# ScouseTom_CS_Shield_R3.net
KiCad netlist of a schematic drawn in EAGLE
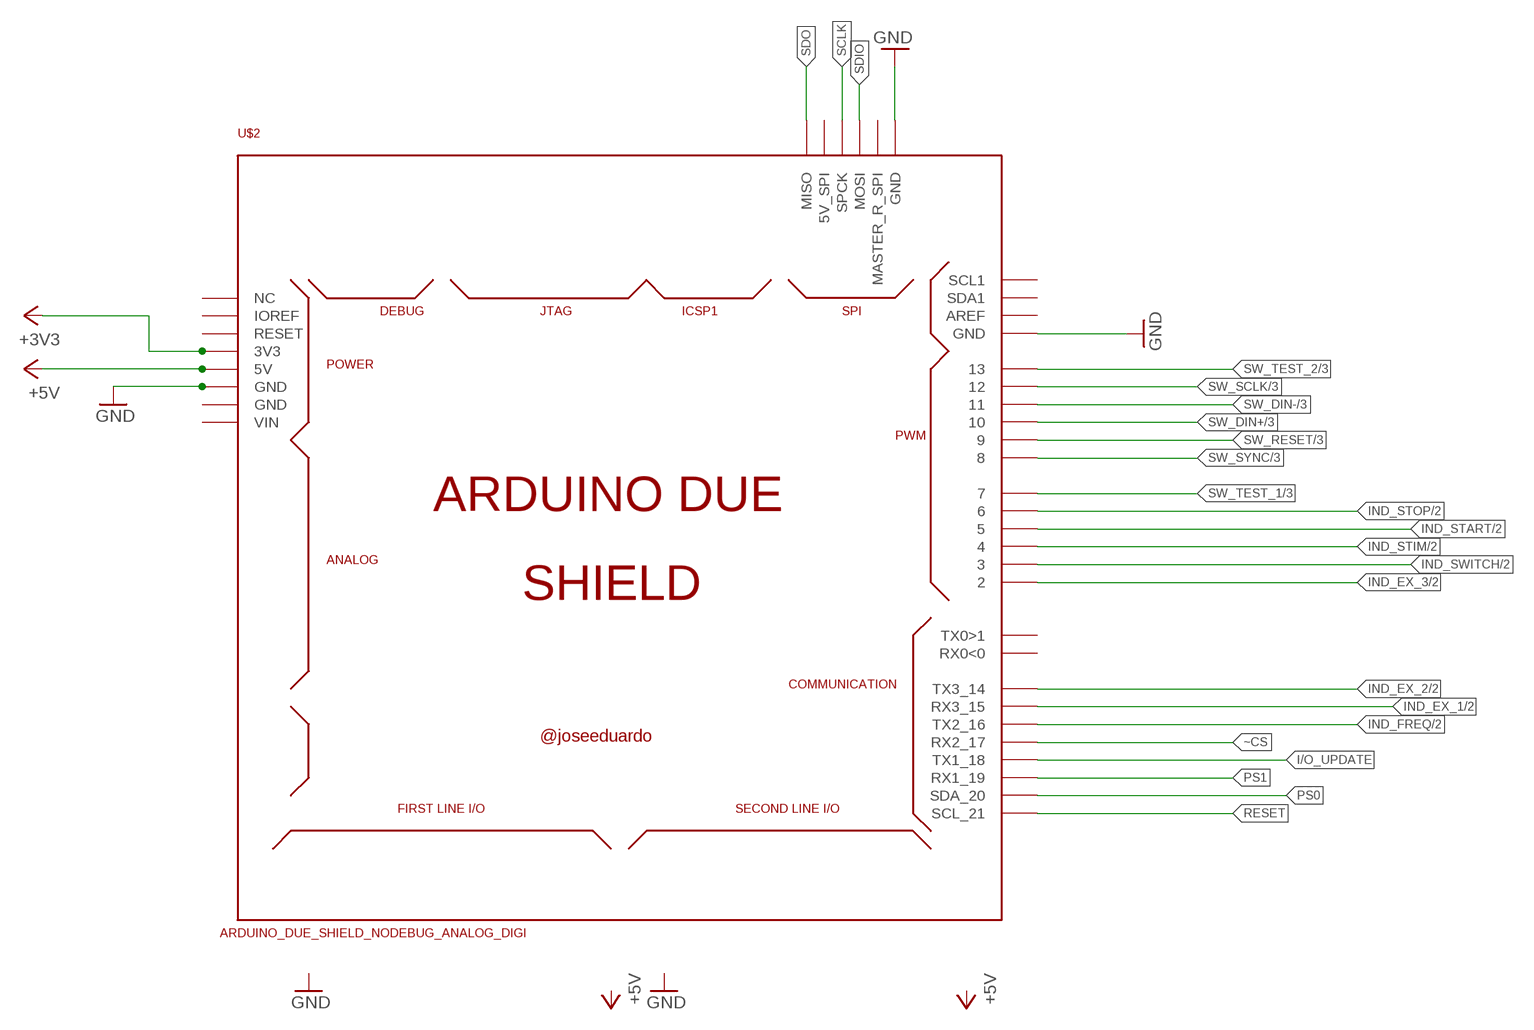
[diagram p0: schematic, sheet 1]
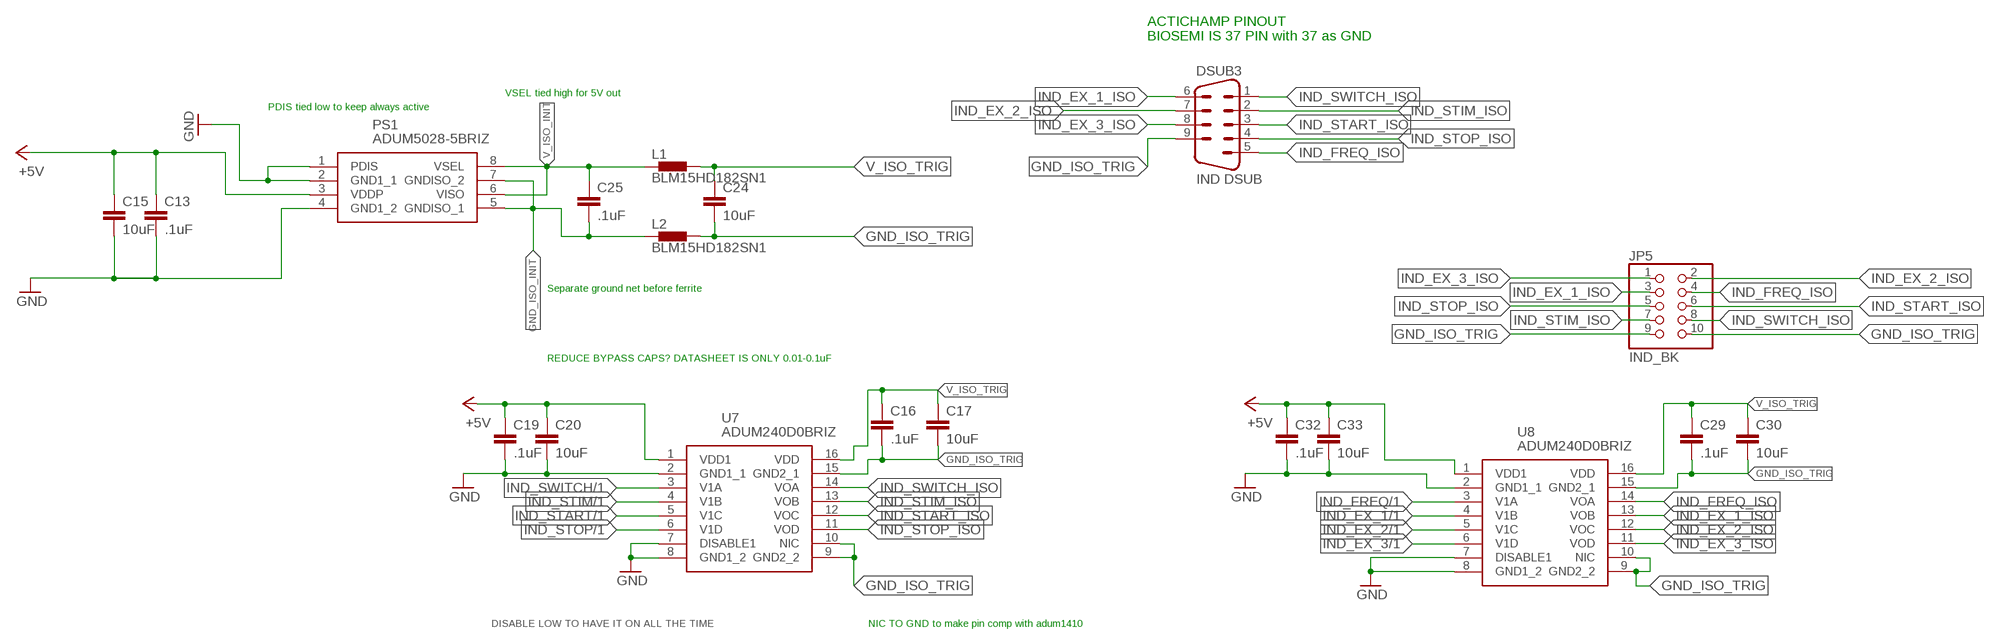
[diagram p1: schematic, sheet 2]
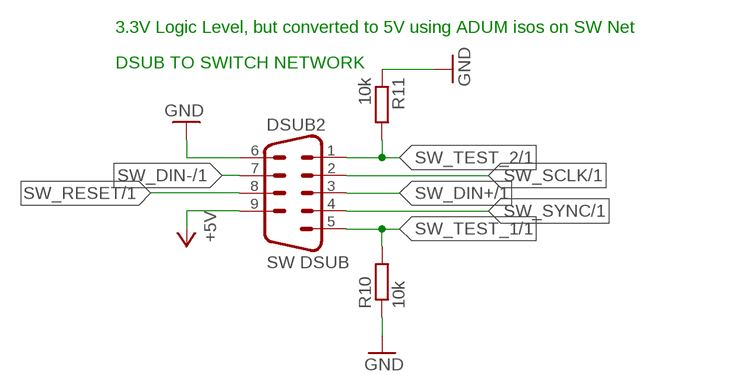
[diagram p2: schematic, sheet 3]
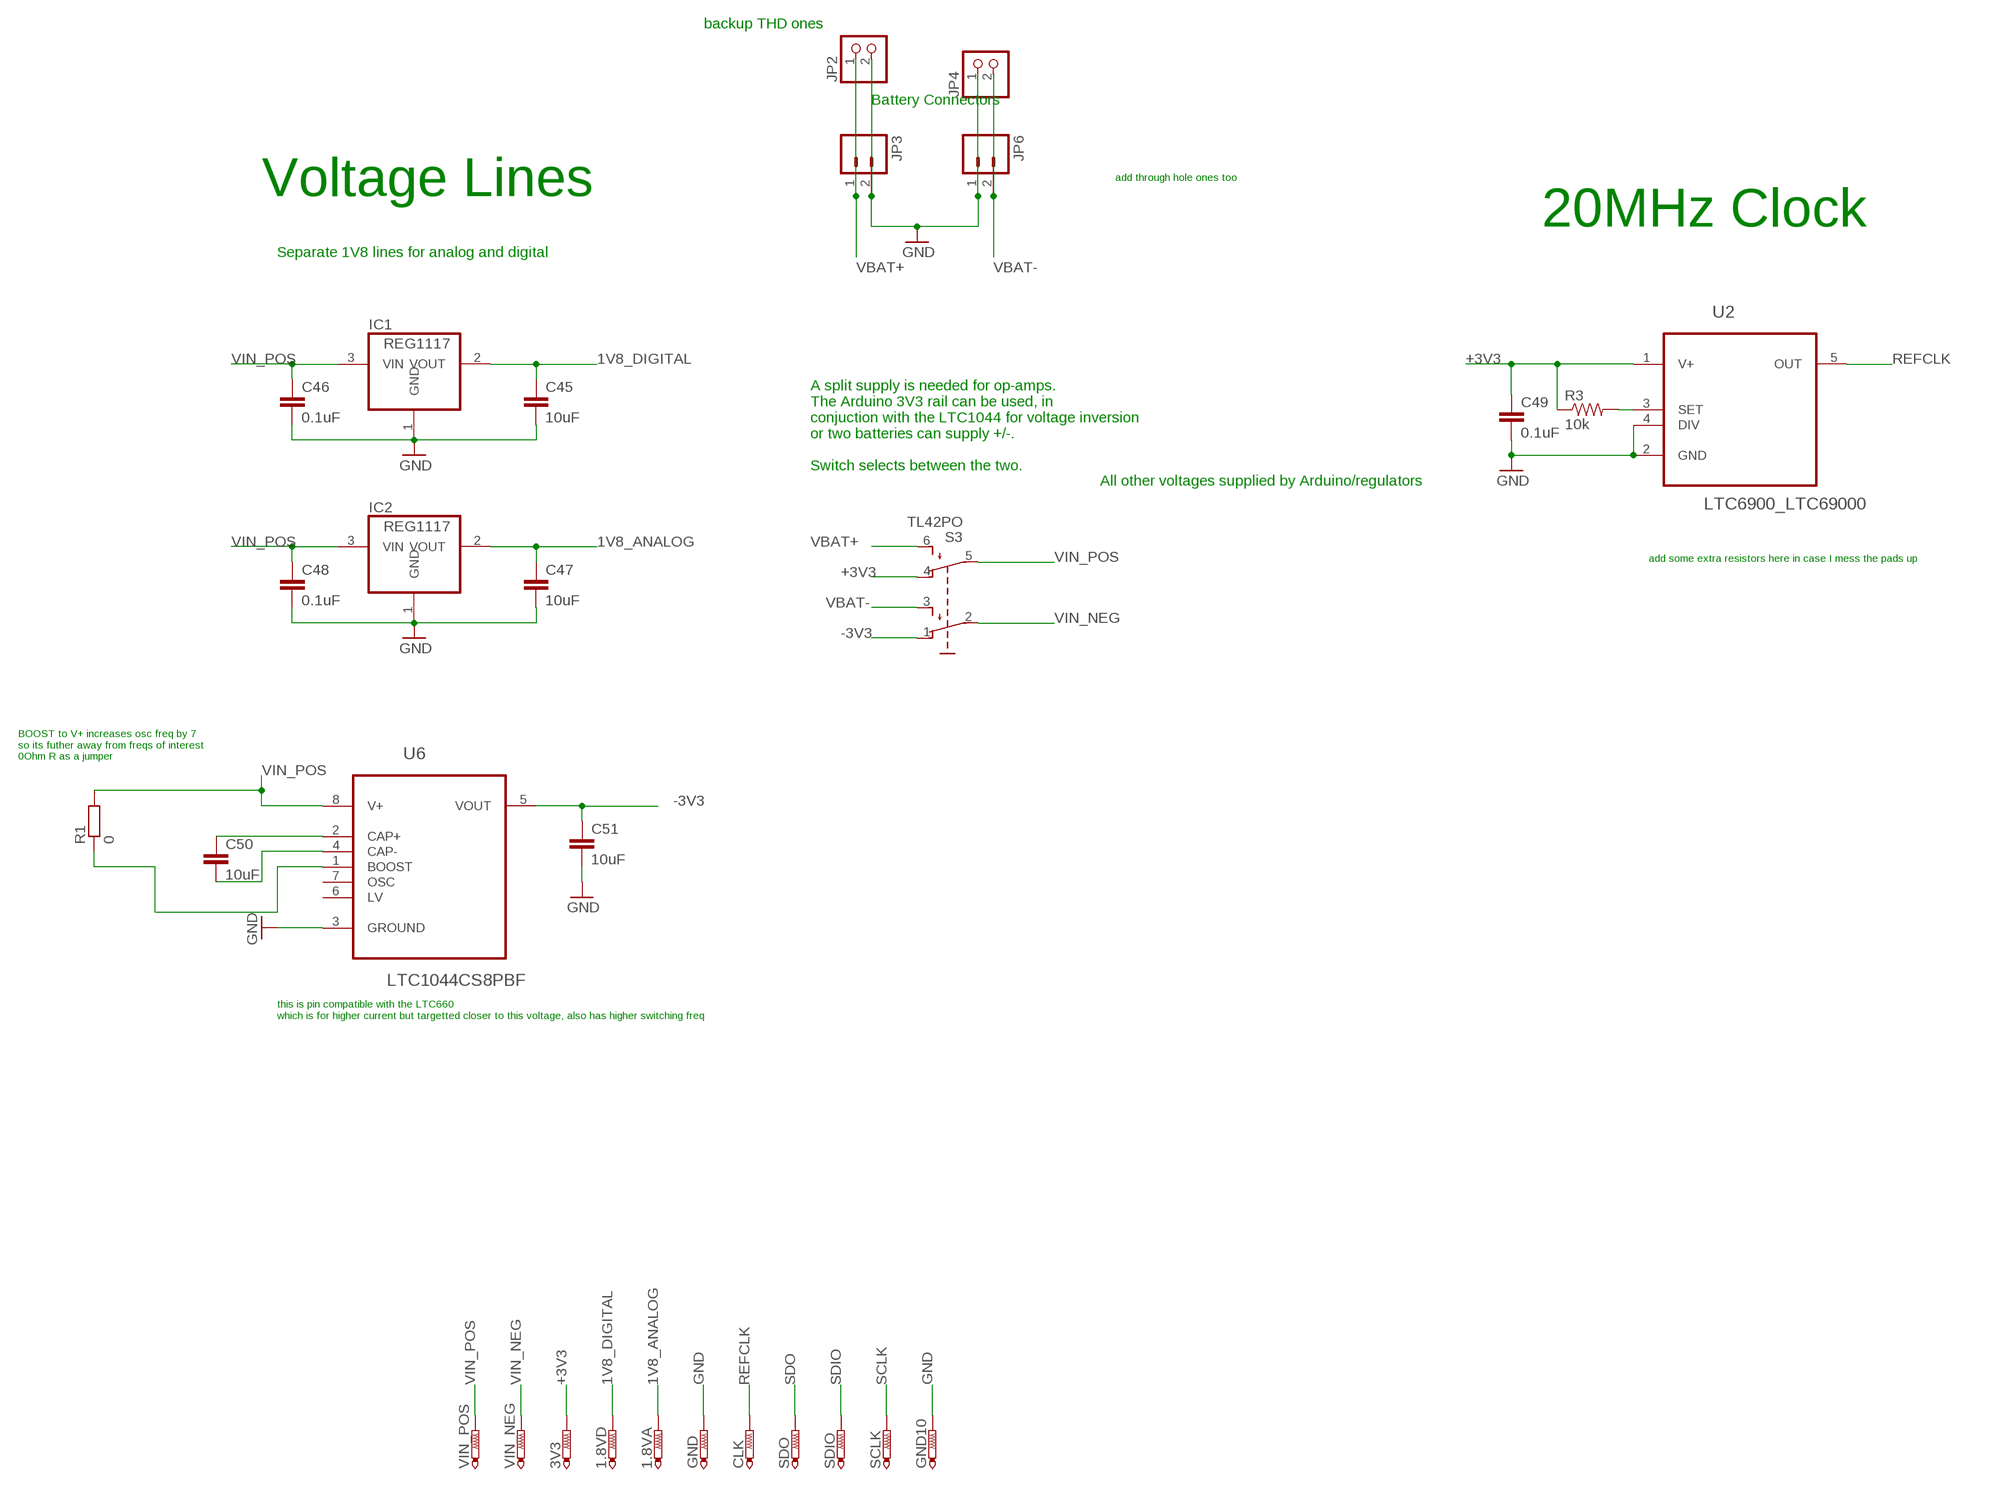
[diagram p3: schematic, sheet 4]
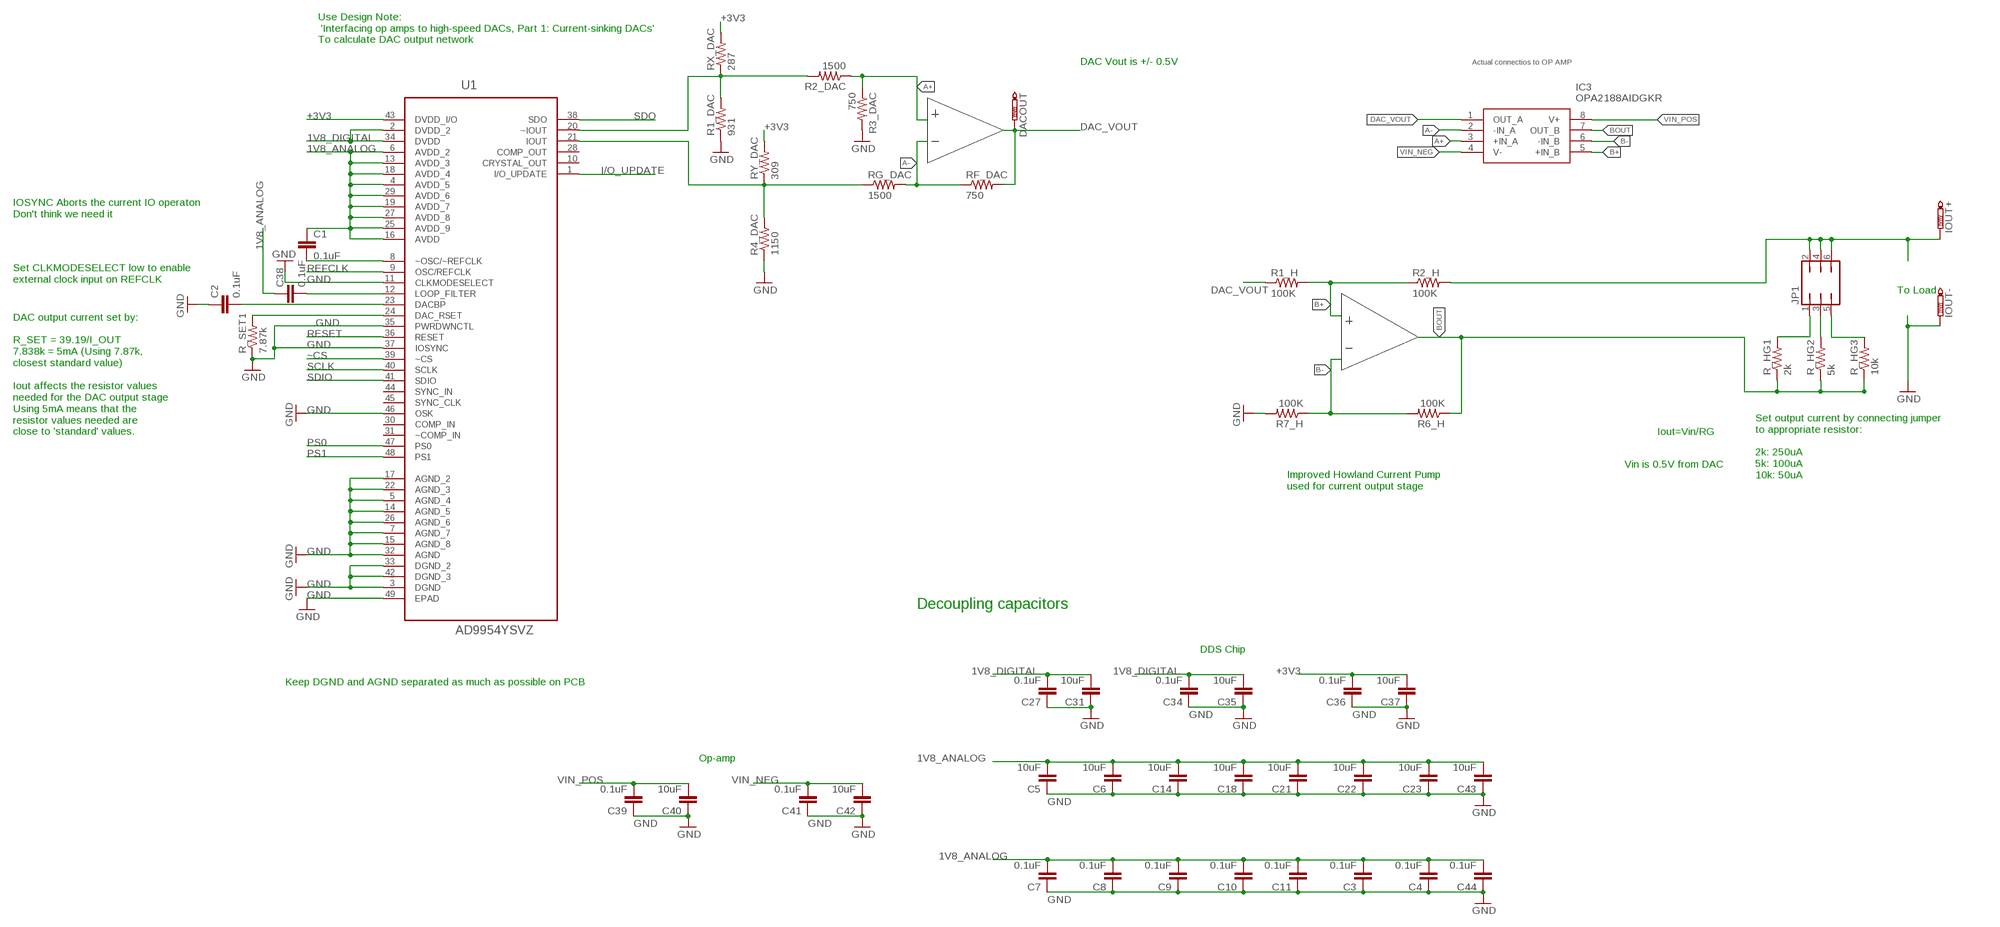
[diagram p4: schematic, sheet 5]

(export (version "E")
  (design (tool "Eeschema 10.0.6"))
  (components
    (comp (ref "C13")
      (value ".1uF")
      (footprint "eagle-import:C0603")
      (libsource (lib "eagle-import") (part "C-EUC0603"))
    )
    (comp (ref "C15")
      (value "10uF")
      (footprint "eagle-import:C0603")
      (libsource (lib "eagle-import") (part "C-EUC0603"))
    )
    (comp (ref "C16")
      (value ".1uF")
      (footprint "eagle-import:C0603")
      (libsource (lib "eagle-import") (part "C-EUC0603"))
    )
    (comp (ref "C17")
      (value "10uF")
      (footprint "eagle-import:C0603")
      (libsource (lib "eagle-import") (part "C-EUC0603"))
    )
    (comp (ref "C19")
      (value ".1uF")
      (footprint "eagle-import:C0603")
      (libsource (lib "eagle-import") (part "C-EUC0603"))
    )
    (comp (ref "C20")
      (value "10uF")
      (footprint "eagle-import:C0603")
      (libsource (lib "eagle-import") (part "C-EUC0603"))
    )
    (comp (ref "C24")
      (value "10uF")
      (footprint "eagle-import:C0603")
      (libsource (lib "eagle-import") (part "C-EUC0603"))
    )
    (comp (ref "C25")
      (value ".1uF")
      (footprint "eagle-import:C0603")
      (libsource (lib "eagle-import") (part "C-EUC0603"))
    )
    (comp (ref "C29")
      (value ".1uF")
      (footprint "eagle-import:C0603")
      (libsource (lib "eagle-import") (part "C-EUC0603"))
    )
    (comp (ref "C30")
      (value "10uF")
      (footprint "eagle-import:C0603")
      (libsource (lib "eagle-import") (part "C-EUC0603"))
    )
    (comp (ref "C32")
      (value ".1uF")
      (footprint "eagle-import:C0603")
      (libsource (lib "eagle-import") (part "C-EUC0603"))
    )
    (comp (ref "C33")
      (value "10uF")
      (footprint "eagle-import:C0603")
      (libsource (lib "eagle-import") (part "C-EUC0603"))
    )
    (comp (ref "DSUB3")
      (value "IND DSUB")
      (footprint "eagle-import:DSUB9")
      (libsource (lib "eagle-import") (part "ScouseTom_New_DSUB9RA"))
    )
    (comp (ref "JP5")
      (value "IND_BK")
      (footprint "eagle-import:2X05")
      (libsource (lib "eagle-import") (part "PINHD-2X5"))
    )
    (comp (ref "L1")
      (value "BLM15HD182SN1")
      (footprint "eagle-import:0402")
      (libsource (lib "eagle-import") (part "BLM15HD182SN1"))
    )
    (comp (ref "L2")
      (value "BLM15HD182SN1")
      (footprint "eagle-import:0402")
      (libsource (lib "eagle-import") (part "BLM15HD182SN1"))
    )
    (comp (ref "PS1")
      (value "ADUM5028-5BRIZ")
      (footprint "eagle-import:SOIC127P1031X265-8N")
      (fields (field (name "MOUSER_PART_NUMBER") "584-ADUM5028-5BRIZ"))
      (libsource (lib "eagle-import") (part "ADUM5028-5BRIZ"))
    )
    (comp (ref "U7")
      (value "ADUM240D0BRIZ")
      (footprint "eagle-import:SOIC127P1032X265-16N")
      (libsource (lib "eagle-import") (part "ADUM240D0BRIZ"))
    )
    (comp (ref "U8")
      (value "ADUM240D0BRIZ")
      (footprint "eagle-import:SOIC127P1032X265-16N")
      (libsource (lib "eagle-import") (part "ADUM240D0BRIZ"))
    )
    (comp (ref "U$2")
      (value "ARDUINO_DUE_SHIELD_NODEBUG_ANALOG_DIGI")
      (footprint "eagle-import:ARDUINO_DUE_SHIELD_NODEBUG_ANALOG_DIG")
      (libsource (lib "eagle-import") (part "ARDUINO_DUE_SHIELD_NODEBUG_ANALOG_DIGI"))
    )
    (comp (ref "C1")
      (value "0.1uF")
      (footprint "eagle-import:C0603")
      (libsource (lib "eagle-import") (part "C-EUC0603"))
    )
    (comp (ref "C2")
      (value "0.1uF")
      (footprint "eagle-import:C0603")
      (libsource (lib "eagle-import") (part "C-EUC0603"))
    )
    (comp (ref "C3")
      (value "0.1uF")
      (footprint "eagle-import:C0603")
      (libsource (lib "eagle-import") (part "C-EUC0603"))
    )
    (comp (ref "C4")
      (value "0.1uF")
      (footprint "eagle-import:C0603")
      (libsource (lib "eagle-import") (part "C-EUC0603"))
    )
    (comp (ref "C5")
      (value "10uF")
      (footprint "eagle-import:C0603")
      (libsource (lib "eagle-import") (part "C-EUC0603"))
    )
    (comp (ref "C6")
      (value "10uF")
      (footprint "eagle-import:C0603")
      (libsource (lib "eagle-import") (part "C-EUC0603"))
    )
    (comp (ref "C7")
      (value "0.1uF")
      (footprint "eagle-import:C0603")
      (libsource (lib "eagle-import") (part "C-EUC0603"))
    )
    (comp (ref "C8")
      (value "0.1uF")
      (footprint "eagle-import:C0603")
      (libsource (lib "eagle-import") (part "C-EUC0603"))
    )
    (comp (ref "C9")
      (value "0.1uF")
      (footprint "eagle-import:C0603")
      (libsource (lib "eagle-import") (part "C-EUC0603"))
    )
    (comp (ref "C10")
      (value "0.1uF")
      (footprint "eagle-import:C0603")
      (libsource (lib "eagle-import") (part "C-EUC0603"))
    )
    (comp (ref "C11")
      (value "0.1uF")
      (footprint "eagle-import:C0603")
      (libsource (lib "eagle-import") (part "C-EUC0603"))
    )
    (comp (ref "C14")
      (value "10uF")
      (footprint "eagle-import:C0603")
      (libsource (lib "eagle-import") (part "C-EUC0603"))
    )
    (comp (ref "C18")
      (value "10uF")
      (footprint "eagle-import:C0603")
      (libsource (lib "eagle-import") (part "C-EUC0603"))
    )
    (comp (ref "C21")
      (value "10uF")
      (footprint "eagle-import:C0603")
      (libsource (lib "eagle-import") (part "C-EUC0603"))
    )
    (comp (ref "C22")
      (value "10uF")
      (footprint "eagle-import:C0603")
      (libsource (lib "eagle-import") (part "C-EUC0603"))
    )
    (comp (ref "C23")
      (value "10uF")
      (footprint "eagle-import:C0603")
      (libsource (lib "eagle-import") (part "C-EUC0603"))
    )
    (comp (ref "C27")
      (value "0.1uF")
      (footprint "eagle-import:C0603")
      (libsource (lib "eagle-import") (part "C-EUC0603"))
    )
    (comp (ref "C31")
      (value "10uF")
      (footprint "eagle-import:C0603")
      (libsource (lib "eagle-import") (part "C-EUC0603"))
    )
    (comp (ref "C34")
      (value "0.1uF")
      (footprint "eagle-import:C0603")
      (libsource (lib "eagle-import") (part "C-EUC0603"))
    )
    (comp (ref "C35")
      (value "10uF")
      (footprint "eagle-import:C0603")
      (libsource (lib "eagle-import") (part "C-EUC0603"))
    )
    (comp (ref "C36")
      (value "0.1uF")
      (footprint "eagle-import:C0603")
      (libsource (lib "eagle-import") (part "C-EUC0603"))
    )
    (comp (ref "C37")
      (value "10uF")
      (footprint "eagle-import:C0603")
      (libsource (lib "eagle-import") (part "C-EUC0603"))
    )
    (comp (ref "C38")
      (value "0.1uF")
      (footprint "eagle-import:C0603")
      (libsource (lib "eagle-import") (part "C-EUC0603"))
    )
    (comp (ref "C39")
      (value "0.1uF")
      (footprint "eagle-import:C0603")
      (libsource (lib "eagle-import") (part "C-EUC0603"))
    )
    (comp (ref "C40")
      (value "10uF")
      (footprint "eagle-import:C0603")
      (libsource (lib "eagle-import") (part "C-EUC0603"))
    )
    (comp (ref "C41")
      (value "0.1uF")
      (footprint "eagle-import:C0603")
      (libsource (lib "eagle-import") (part "C-EUC0603"))
    )
    (comp (ref "C42")
      (value "10uF")
      (footprint "eagle-import:C0603")
      (libsource (lib "eagle-import") (part "C-EUC0603"))
    )
    (comp (ref "C43")
      (value "10uF")
      (footprint "eagle-import:C0603")
      (libsource (lib "eagle-import") (part "C-EUC0603"))
    )
    (comp (ref "C44")
      (value "0.1uF")
      (footprint "eagle-import:C0603")
      (libsource (lib "eagle-import") (part "C-EUC0603"))
    )
    (comp (ref "DACOUT")
      (value "PTR1PAD1-13")
      (footprint "eagle-import:P1-13")
      (libsource (lib "eagle-import") (part "PTR1PAD1-13"))
    )
    (comp (ref "IC3")
      (value "OPA2188AIDGKR")
      (footprint "eagle-import:SOP65P490X110-8N")
      (libsource (lib "eagle-import") (part "OPA2188AIDGKR"))
    )
    (comp (ref "IOUT+")
      (value "PTR1PAD1-13")
      (footprint "eagle-import:P1-13")
      (libsource (lib "eagle-import") (part "PTR1PAD1-13"))
    )
    (comp (ref "IOUT-")
      (value "PTR1PAD1-13")
      (footprint "eagle-import:P1-13")
      (libsource (lib "eagle-import") (part "PTR1PAD1-13"))
    )
    (comp (ref "JP1")
      (value "JP3Q")
      (footprint "eagle-import:JP3Q")
      (libsource (lib "eagle-import") (part "JP3Q"))
    )
    (comp (ref "R1_DAC")
      (value "931")
      (footprint "eagle-import:R0805")
      (libsource (lib "eagle-import") (part "R-US_R0805"))
    )
    (comp (ref "R1_H")
      (value "100K")
      (footprint "eagle-import:R0805")
      (libsource (lib "eagle-import") (part "R-US_R0805"))
    )
    (comp (ref "R2_DAC")
      (value "1500")
      (footprint "eagle-import:R0805")
      (libsource (lib "eagle-import") (part "R-US_R0805"))
    )
    (comp (ref "R2_H")
      (value "100K")
      (footprint "eagle-import:R0805")
      (libsource (lib "eagle-import") (part "R-US_R0805"))
    )
    (comp (ref "R3_DAC")
      (value "750")
      (footprint "eagle-import:R0805")
      (libsource (lib "eagle-import") (part "R-US_R0805"))
    )
    (comp (ref "R4_DAC")
      (value "1150")
      (footprint "eagle-import:R0805")
      (libsource (lib "eagle-import") (part "R-US_R0805"))
    )
    (comp (ref "R6_H")
      (value "100K")
      (footprint "eagle-import:R0805")
      (libsource (lib "eagle-import") (part "R-US_R0805"))
    )
    (comp (ref "R7_H")
      (value "100K")
      (footprint "eagle-import:R0805")
      (libsource (lib "eagle-import") (part "R-US_R0805"))
    )
    (comp (ref "RF_DAC")
      (value "750")
      (footprint "eagle-import:R0805")
      (libsource (lib "eagle-import") (part "R-US_R0805"))
    )
    (comp (ref "RG_DAC")
      (value "1500")
      (footprint "eagle-import:R0805")
      (libsource (lib "eagle-import") (part "R-US_R0805"))
    )
    (comp (ref "RX_DAC")
      (value "287")
      (footprint "eagle-import:R0805")
      (libsource (lib "eagle-import") (part "R-US_R0805"))
    )
    (comp (ref "RY_DAC")
      (value "309")
      (footprint "eagle-import:R0805")
      (libsource (lib "eagle-import") (part "R-US_R0805"))
    )
    (comp (ref "R_HG1")
      (value "2k")
      (footprint "eagle-import:R0805")
      (libsource (lib "eagle-import") (part "R-US_R0805"))
    )
    (comp (ref "R_HG2")
      (value "5k")
      (footprint "eagle-import:R0805")
      (libsource (lib "eagle-import") (part "R-US_R0805"))
    )
    (comp (ref "R_HG3")
      (value "10k")
      (footprint "eagle-import:R0805")
      (libsource (lib "eagle-import") (part "R-US_R0805"))
    )
    (comp (ref "R_SET1")
      (value "7.87k")
      (footprint "eagle-import:R0805")
      (libsource (lib "eagle-import") (part "R-US_R0805"))
    )
    (comp (ref "U1")
      (value "AD9954YSVZ")
      (footprint "eagle-import:QFP50P900X900X120-49N")
      (libsource (lib "eagle-import") (part "AD9954YSVZ"))
    )
    (comp (ref "1.8VA")
      (value "PTR1PAD1-13")
      (footprint "eagle-import:P1-13")
      (libsource (lib "eagle-import") (part "PTR1PAD1-13"))
    )
    (comp (ref "1.8VD")
      (value "PTR1PAD1-13")
      (footprint "eagle-import:P1-13")
      (libsource (lib "eagle-import") (part "PTR1PAD1-13"))
    )
    (comp (ref "3V3")
      (value "PTR1PAD1-13")
      (footprint "eagle-import:P1-13")
      (libsource (lib "eagle-import") (part "PTR1PAD1-13"))
    )
    (comp (ref "C45")
      (value "10uF")
      (footprint "eagle-import:C0603")
      (libsource (lib "eagle-import") (part "C-EUC0603"))
    )
    (comp (ref "C46")
      (value "0.1uF")
      (footprint "eagle-import:C0603")
      (libsource (lib "eagle-import") (part "C-EUC0603"))
    )
    (comp (ref "C47")
      (value "10uF")
      (footprint "eagle-import:C0603")
      (libsource (lib "eagle-import") (part "C-EUC0603"))
    )
    (comp (ref "C48")
      (value "0.1uF")
      (footprint "eagle-import:C0603")
      (libsource (lib "eagle-import") (part "C-EUC0603"))
    )
    (comp (ref "C49")
      (value "0.1uF")
      (footprint "eagle-import:C0603")
      (libsource (lib "eagle-import") (part "C-EUC0603"))
    )
    (comp (ref "C50")
      (value "10uF")
      (footprint "eagle-import:C0603")
      (libsource (lib "eagle-import") (part "C-EUC0603"))
    )
    (comp (ref "C51")
      (value "10uF")
      (footprint "eagle-import:C0603")
      (libsource (lib "eagle-import") (part "C-EUC0603"))
    )
    (comp (ref "CLK")
      (value "PTR1PAD1-13")
      (footprint "eagle-import:P1-13")
      (libsource (lib "eagle-import") (part "PTR1PAD1-13"))
    )
    (comp (ref "GND")
      (value "PTR1PAD1-13")
      (footprint "eagle-import:P1-13")
      (libsource (lib "eagle-import") (part "PTR1PAD1-13"))
    )
    (comp (ref "GND10")
      (value "PTR1PAD1-13")
      (footprint "eagle-import:P1-13")
      (libsource (lib "eagle-import") (part "PTR1PAD1-13"))
    )
    (comp (ref "IC1")
      (value "REG1117")
      (footprint "eagle-import:SOT223")
      (libsource (lib "eagle-import") (part "REG1117"))
    )
    (comp (ref "IC2")
      (value "REG1117")
      (footprint "eagle-import:SOT223")
      (libsource (lib "eagle-import") (part "REG1117"))
    )
    (comp (ref "JP2")
      (value "PINHD-1X2")
      (footprint "eagle-import:1X02")
      (libsource (lib "eagle-import") (part "PINHD-1X2"))
    )
    (comp (ref "JP3")
      (value "M02-JST-2MM-SMT")
      (footprint "eagle-import:JST-2-SMD")
      (libsource (lib "eagle-import") (part "M02-JST-2MM-SMT"))
    )
    (comp (ref "JP4")
      (value "PINHD-1X2")
      (footprint "eagle-import:1X02")
      (libsource (lib "eagle-import") (part "PINHD-1X2"))
    )
    (comp (ref "JP6")
      (value "M02-JST-2MM-SMT")
      (footprint "eagle-import:JST-2-SMD")
      (libsource (lib "eagle-import") (part "M02-JST-2MM-SMT"))
    )
    (comp (ref "R1")
      (value "0")
      (footprint "eagle-import:R0805")
      (libsource (lib "eagle-import") (part "R-EU_R0805"))
    )
    (comp (ref "R3")
      (value "10k")
      (footprint "eagle-import:R0805")
      (libsource (lib "eagle-import") (part "R-US_R0805"))
    )
    (comp (ref "S3")
      (value "TL42PO")
      (footprint "eagle-import:TL4XPO")
      (libsource (lib "eagle-import") (part "TL42PO"))
    )
    (comp (ref "SCLK")
      (value "PTR1PAD1-13")
      (footprint "eagle-import:P1-13")
      (libsource (lib "eagle-import") (part "PTR1PAD1-13"))
    )
    (comp (ref "SDIO")
      (value "PTR1PAD1-13")
      (footprint "eagle-import:P1-13")
      (libsource (lib "eagle-import") (part "PTR1PAD1-13"))
    )
    (comp (ref "SDO")
      (value "PTR1PAD1-13")
      (footprint "eagle-import:P1-13")
      (libsource (lib "eagle-import") (part "PTR1PAD1-13"))
    )
    (comp (ref "U2")
      (value "LTC6900_LTC69000")
      (footprint "eagle-import:LTC6900_SOT23-5L")
      (libsource (lib "eagle-import") (part "LTC6900_LTC69000"))
    )
    (comp (ref "U6")
      (value "LTC1044CS8PBF")
      (footprint "eagle-import:SOIC127P600X175-8N")
      (fields (field (name "MPN") "LTC1044CS8#PBF"))
      (libsource (lib "eagle-import") (part "LTC1044CS8PBF"))
    )
    (comp (ref "VIN_NEG")
      (value "PTR1PAD1-13")
      (footprint "eagle-import:P1-13")
      (libsource (lib "eagle-import") (part "PTR1PAD1-13"))
    )
    (comp (ref "VIN_POS")
      (value "PTR1PAD1-13")
      (footprint "eagle-import:P1-13")
      (libsource (lib "eagle-import") (part "PTR1PAD1-13"))
    )
    (comp (ref "DSUB2")
      (value "SW DSUB")
      (footprint "eagle-import:DSUB9")
      (libsource (lib "eagle-import") (part "DSUB9RA"))
    )
    (comp (ref "R10")
      (value "10k")
      (footprint "eagle-import:R0805")
      (libsource (lib "eagle-import") (part "R-EU_R0805"))
    )
    (comp (ref "R11")
      (value "10k")
      (footprint "eagle-import:R0805")
      (libsource (lib "eagle-import") (part "R-EU_R0805"))
    )
  )
  (nets
    (net (code "1") (name "+3V3") (class "Default")
      (node (ref "3V3") (pin "TP") (pinfunction "TP_TP") (pintype "input"))
      (node (ref "C36") (pin "2") (pinfunction "2_2") (pintype "passive"))
      (node (ref "C37") (pin "2") (pinfunction "2_2") (pintype "passive"))
      (node (ref "C49") (pin "1") (pinfunction "1_1") (pintype "passive"))
      (node (ref "R3") (pin "1") (pinfunction "1_1") (pintype "passive"))
      (node (ref "RX_DAC") (pin "2") (pinfunction "2_2") (pintype "passive"))
      (node (ref "RY_DAC") (pin "2") (pinfunction "2_2") (pintype "passive"))
      (node (ref "S3") (pin "4") (pinfunction "O1_4") (pintype "passive"))
      (node (ref "U$2") (pin "3V3") (pinfunction "3V3_3V3") (pintype "bidirectional"))
      (node (ref "U1") (pin "43") (pinfunction "DVDD_I/O_43") (pintype "power_in"))
      (node (ref "U2") (pin "1") (pinfunction "V+_1") (pintype "power_in"))
    )
    (net (code "2") (name "+5V") (class "Default")
      (node (ref "C13") (pin "1") (pinfunction "1_1") (pintype "passive"))
      (node (ref "C15") (pin "1") (pinfunction "1_1") (pintype "passive"))
      (node (ref "C19") (pin "1") (pinfunction "1_1") (pintype "passive"))
      (node (ref "C20") (pin "1") (pinfunction "1_1") (pintype "passive"))
      (node (ref "C32") (pin "1") (pinfunction "1_1") (pintype "passive"))
      (node (ref "C33") (pin "1") (pinfunction "1_1") (pintype "passive"))
      (node (ref "DSUB2") (pin "9") (pinfunction "9_9") (pintype "passive"))
      (node (ref "PS1") (pin "3") (pinfunction "VDDP_3") (pintype "bidirectional"))
      (node (ref "U$2") (pin "5V0") (pinfunction "5V_5V0") (pintype "bidirectional"))
      (node (ref "U7") (pin "1") (pinfunction "VDD1_1") (pintype "power_in"))
      (node (ref "U8") (pin "1") (pinfunction "VDD1_1") (pintype "power_in"))
    )
    (net (code "3") (name "-3V3") (class "Default")
      (node (ref "C51") (pin "1") (pinfunction "1_1") (pintype "passive"))
      (node (ref "S3") (pin "1") (pinfunction "O_1") (pintype "passive"))
      (node (ref "U6") (pin "5") (pinfunction "VOUT_5") (pintype "output"))
    )
    (net (code "4") (name "1V8_ANALOG") (class "Default")
      (node (ref "1.8VA") (pin "TP") (pinfunction "TP_TP") (pintype "input"))
      (node (ref "C1") (pin "1") (pinfunction "1_1") (pintype "passive"))
      (node (ref "C10") (pin "2") (pinfunction "2_2") (pintype "passive"))
      (node (ref "C11") (pin "2") (pinfunction "2_2") (pintype "passive"))
      (node (ref "C14") (pin "2") (pinfunction "2_2") (pintype "passive"))
      (node (ref "C18") (pin "2") (pinfunction "2_2") (pintype "passive"))
      (node (ref "C21") (pin "2") (pinfunction "2_2") (pintype "passive"))
      (node (ref "C22") (pin "2") (pinfunction "2_2") (pintype "passive"))
      (node (ref "C23") (pin "2") (pinfunction "2_2") (pintype "passive"))
      (node (ref "C3") (pin "2") (pinfunction "2_2") (pintype "passive"))
      (node (ref "C38") (pin "1") (pinfunction "1_1") (pintype "passive"))
      (node (ref "C4") (pin "2") (pinfunction "2_2") (pintype "passive"))
      (node (ref "C43") (pin "2") (pinfunction "2_2") (pintype "passive"))
      (node (ref "C44") (pin "2") (pinfunction "2_2") (pintype "passive"))
      (node (ref "C47") (pin "1") (pinfunction "1_1") (pintype "passive"))
      (node (ref "C5") (pin "2") (pinfunction "2_2") (pintype "passive"))
      (node (ref "C6") (pin "2") (pinfunction "2_2") (pintype "passive"))
      (node (ref "C7") (pin "2") (pinfunction "2_2") (pintype "passive"))
      (node (ref "C8") (pin "2") (pinfunction "2_2") (pintype "passive"))
      (node (ref "C9") (pin "2") (pinfunction "2_2") (pintype "passive"))
      (node (ref "IC2") (pin "2") (pinfunction "VOUT_2") (pintype "output"))
      (node (ref "U1") (pin "13") (pinfunction "AVDD_3_13") (pintype "power_in"))
      (node (ref "U1") (pin "16") (pinfunction "AVDD_16") (pintype "power_in"))
      (node (ref "U1") (pin "18") (pinfunction "AVDD_4_18") (pintype "power_in"))
      (node (ref "U1") (pin "19") (pinfunction "AVDD_7_19") (pintype "power_in"))
      (node (ref "U1") (pin "25") (pinfunction "AVDD_9_25") (pintype "power_in"))
      (node (ref "U1") (pin "27") (pinfunction "AVDD_8_27") (pintype "power_in"))
      (node (ref "U1") (pin "29") (pinfunction "AVDD_6_29") (pintype "power_in"))
      (node (ref "U1") (pin "4") (pinfunction "AVDD_5_4") (pintype "power_in"))
      (node (ref "U1") (pin "6") (pinfunction "AVDD_2_6") (pintype "power_in"))
    )
    (net (code "5") (name "1V8_DIGITAL") (class "Default")
      (node (ref "1.8VD") (pin "TP") (pinfunction "TP_TP") (pintype "input"))
      (node (ref "C27") (pin "2") (pinfunction "2_2") (pintype "passive"))
      (node (ref "C31") (pin "2") (pinfunction "2_2") (pintype "passive"))
      (node (ref "C34") (pin "2") (pinfunction "2_2") (pintype "passive"))
      (node (ref "C35") (pin "2") (pinfunction "2_2") (pintype "passive"))
      (node (ref "C45") (pin "1") (pinfunction "1_1") (pintype "passive"))
      (node (ref "IC1") (pin "2") (pinfunction "VOUT_2") (pintype "output"))
      (node (ref "U1") (pin "2") (pinfunction "DVDD_2_2") (pintype "power_in"))
      (node (ref "U1") (pin "34") (pinfunction "DVDD_34") (pintype "power_in"))
    )
    (net (code "6") (name "A+") (class "Default")
      (node (ref "IC3") (pin "3") (pinfunction "+IN_A_3") (pintype "input"))
      (node (ref "R2_DAC") (pin "1") (pinfunction "1_1") (pintype "passive"))
      (node (ref "R3_DAC") (pin "1") (pinfunction "1_1") (pintype "passive"))
    )
    (net (code "7") (name "A-") (class "Default")
      (node (ref "IC3") (pin "2") (pinfunction "-IN_A_2") (pintype "input"))
      (node (ref "RF_DAC") (pin "1") (pinfunction "1_1") (pintype "passive"))
      (node (ref "RG_DAC") (pin "2") (pinfunction "2_2") (pintype "passive"))
    )
    (net (code "8") (name "B+") (class "Default")
      (node (ref "IC3") (pin "5") (pinfunction "+IN_B_5") (pintype "input"))
      (node (ref "R1_H") (pin "2") (pinfunction "2_2") (pintype "passive"))
      (node (ref "R2_H") (pin "1") (pinfunction "1_1") (pintype "passive"))
    )
    (net (code "9") (name "B-") (class "Default")
      (node (ref "IC3") (pin "6") (pinfunction "-IN_B_6") (pintype "input"))
      (node (ref "R6_H") (pin "2") (pinfunction "2_2") (pintype "passive"))
      (node (ref "R7_H") (pin "1") (pinfunction "1_1") (pintype "passive"))
    )
    (net (code "10") (name "BOUT") (class "Default")
      (node (ref "IC3") (pin "7") (pinfunction "OUT_B_7") (pintype "output"))
      (node (ref "R6_H") (pin "1") (pinfunction "1_1") (pintype "passive"))
      (node (ref "R_HG1") (pin "1") (pinfunction "1_1") (pintype "passive"))
      (node (ref "R_HG2") (pin "1") (pinfunction "1_1") (pintype "passive"))
      (node (ref "R_HG3") (pin "1") (pinfunction "1_1") (pintype "passive"))
    )
    (net (code "11") (name "DAC_VOUT") (class "Default")
      (node (ref "DACOUT") (pin "TP") (pinfunction "TP_TP") (pintype "input"))
      (node (ref "IC3") (pin "1") (pinfunction "OUT_A_1") (pintype "output"))
      (node (ref "R1_H") (pin "1") (pinfunction "1_1") (pintype "passive"))
      (node (ref "RF_DAC") (pin "2") (pinfunction "2_2") (pintype "passive"))
    )
    (net (code "12") (name "GND") (class "Default")
      (node (ref "C10") (pin "1") (pinfunction "1_1") (pintype "passive"))
      (node (ref "C11") (pin "1") (pinfunction "1_1") (pintype "passive"))
      (node (ref "C13") (pin "2") (pinfunction "2_2") (pintype "passive"))
      (node (ref "C14") (pin "1") (pinfunction "1_1") (pintype "passive"))
      (node (ref "C15") (pin "2") (pinfunction "2_2") (pintype "passive"))
      (node (ref "C18") (pin "1") (pinfunction "1_1") (pintype "passive"))
      (node (ref "C19") (pin "2") (pinfunction "2_2") (pintype "passive"))
      (node (ref "C2") (pin "1") (pinfunction "1_1") (pintype "passive"))
      (node (ref "C20") (pin "2") (pinfunction "2_2") (pintype "passive"))
      (node (ref "C21") (pin "1") (pinfunction "1_1") (pintype "passive"))
      (node (ref "C22") (pin "1") (pinfunction "1_1") (pintype "passive"))
      (node (ref "C23") (pin "1") (pinfunction "1_1") (pintype "passive"))
      (node (ref "C27") (pin "1") (pinfunction "1_1") (pintype "passive"))
      (node (ref "C3") (pin "1") (pinfunction "1_1") (pintype "passive"))
      (node (ref "C31") (pin "1") (pinfunction "1_1") (pintype "passive"))
      (node (ref "C32") (pin "2") (pinfunction "2_2") (pintype "passive"))
      (node (ref "C33") (pin "2") (pinfunction "2_2") (pintype "passive"))
      (node (ref "C34") (pin "1") (pinfunction "1_1") (pintype "passive"))
      (node (ref "C35") (pin "1") (pinfunction "1_1") (pintype "passive"))
      (node (ref "C36") (pin "1") (pinfunction "1_1") (pintype "passive"))
      (node (ref "C37") (pin "1") (pinfunction "1_1") (pintype "passive"))
      (node (ref "C39") (pin "1") (pinfunction "1_1") (pintype "passive"))
      (node (ref "C4") (pin "1") (pinfunction "1_1") (pintype "passive"))
      (node (ref "C40") (pin "1") (pinfunction "1_1") (pintype "passive"))
      (node (ref "C41") (pin "1") (pinfunction "1_1") (pintype "passive"))
      (node (ref "C42") (pin "1") (pinfunction "1_1") (pintype "passive"))
      (node (ref "C43") (pin "1") (pinfunction "1_1") (pintype "passive"))
      (node (ref "C44") (pin "1") (pinfunction "1_1") (pintype "passive"))
      (node (ref "C45") (pin "2") (pinfunction "2_2") (pintype "passive"))
      (node (ref "C46") (pin "2") (pinfunction "2_2") (pintype "passive"))
      (node (ref "C47") (pin "2") (pinfunction "2_2") (pintype "passive"))
      (node (ref "C48") (pin "2") (pinfunction "2_2") (pintype "passive"))
      (node (ref "C49") (pin "2") (pinfunction "2_2") (pintype "passive"))
      (node (ref "C5") (pin "1") (pinfunction "1_1") (pintype "passive"))
      (node (ref "C51") (pin "2") (pinfunction "2_2") (pintype "passive"))
      (node (ref "C6") (pin "1") (pinfunction "1_1") (pintype "passive"))
      (node (ref "C7") (pin "1") (pinfunction "1_1") (pintype "passive"))
      (node (ref "C8") (pin "1") (pinfunction "1_1") (pintype "passive"))
      (node (ref "C9") (pin "1") (pinfunction "1_1") (pintype "passive"))
      (node (ref "DSUB2") (pin "6") (pinfunction "6_6") (pintype "passive"))
      (node (ref "GND") (pin "TP") (pinfunction "TP_TP") (pintype "input"))
      (node (ref "GND10") (pin "TP") (pinfunction "TP_TP") (pintype "input"))
      (node (ref "IC1") (pin "1") (pinfunction "GND_1") (pintype "power_in"))
      (node (ref "IC2") (pin "1") (pinfunction "GND_1") (pintype "power_in"))
      (node (ref "IOUT-") (pin "TP") (pinfunction "TP_TP") (pintype "input"))
      (node (ref "JP2") (pin "2") (pinfunction "2_2") (pintype "passive"))
      (node (ref "JP3") (pin "2") (pinfunction "2_2") (pintype "passive"))
      (node (ref "JP4") (pin "1") (pinfunction "1_1") (pintype "passive"))
      (node (ref "JP6") (pin "1") (pinfunction "1_1") (pintype "passive"))
      (node (ref "PS1") (pin "1") (pinfunction "PDIS_1") (pintype "bidirectional"))
      (node (ref "PS1") (pin "2") (pinfunction "GND1_1_2") (pintype "bidirectional"))
      (node (ref "PS1") (pin "4") (pinfunction "GND1_2_4") (pintype "bidirectional"))
      (node (ref "R10") (pin "1") (pinfunction "1_1") (pintype "passive"))
      (node (ref "R11") (pin "1") (pinfunction "1_1") (pintype "passive"))
      (node (ref "R1_DAC") (pin "1") (pinfunction "1_1") (pintype "passive"))
      (node (ref "R3_DAC") (pin "2") (pinfunction "2_2") (pintype "passive"))
      (node (ref "R4_DAC") (pin "1") (pinfunction "1_1") (pintype "passive"))
      (node (ref "R7_H") (pin "2") (pinfunction "2_2") (pintype "passive"))
      (node (ref "R_SET1") (pin "1") (pinfunction "1_1") (pintype "passive"))
      (node (ref "U$2") (pin "GND") (pinfunction "GND_GND") (pintype "bidirectional"))
      (node (ref "U$2") (pin "GND_4") (pinfunction "GND_GND_4") (pintype "bidirectional"))
      (node (ref "U$2") (pin "GND_5") (pinfunction "GND_GND_5") (pintype "bidirectional"))
      (node (ref "U1") (pin "11") (pinfunction "CLKMODESELECT_11") (pintype "input"))
      (node (ref "U1") (pin "14") (pinfunction "AGND_5_14") (pintype "passive"))
      (node (ref "U1") (pin "15") (pinfunction "AGND_8_15") (pintype "passive"))
      (node (ref "U1") (pin "17") (pinfunction "AGND_2_17") (pintype "passive"))
      (node (ref "U1") (pin "22") (pinfunction "AGND_3_22") (pintype "passive"))
      (node (ref "U1") (pin "26") (pinfunction "AGND_6_26") (pintype "passive"))
      (node (ref "U1") (pin "3") (pinfunction "DGND_3") (pintype "passive"))
      (node (ref "U1") (pin "32") (pinfunction "AGND_32") (pintype "passive"))
      (node (ref "U1") (pin "33") (pinfunction "DGND_2_33") (pintype "passive"))
      (node (ref "U1") (pin "35") (pinfunction "PWRDWNCTL_35") (pintype "input"))
      (node (ref "U1") (pin "37") (pinfunction "IOSYNC_37") (pintype "input"))
      (node (ref "U1") (pin "42") (pinfunction "DGND_3_42") (pintype "passive"))
      (node (ref "U1") (pin "46") (pinfunction "OSK_46") (pintype "input"))
      (node (ref "U1") (pin "49") (pinfunction "EPAD_49") (pintype "passive"))
      (node (ref "U1") (pin "5") (pinfunction "AGND_4_5") (pintype "passive"))
      (node (ref "U1") (pin "7") (pinfunction "AGND_7_7") (pintype "passive"))
      (node (ref "U2") (pin "2") (pinfunction "GND_2") (pintype "passive"))
      (node (ref "U2") (pin "4") (pinfunction "DIV_4") (pintype "input"))
      (node (ref "U6") (pin "3") (pinfunction "GROUND_3") (pintype "passive"))
      (node (ref "U7") (pin "2") (pinfunction "GND1_1_2") (pintype "power_in"))
      (node (ref "U7") (pin "7") (pinfunction "DISABLE1_7") (pintype "bidirectional"))
      (node (ref "U7") (pin "8") (pinfunction "GND1_2_8") (pintype "power_in"))
      (node (ref "U8") (pin "2") (pinfunction "GND1_1_2") (pintype "power_in"))
      (node (ref "U8") (pin "7") (pinfunction "DISABLE1_7") (pintype "bidirectional"))
      (node (ref "U8") (pin "8") (pinfunction "GND1_2_8") (pintype "power_in"))
    )
    (net (code "13") (name "GND_ISO_INIT") (class "Default")
      (node (ref "C25") (pin "2") (pinfunction "2_2") (pintype "passive"))
      (node (ref "L2") (pin "1") (pinfunction "1_1") (pintype "passive"))
      (node (ref "PS1") (pin "5") (pinfunction "GNDISO_1_5") (pintype "bidirectional"))
      (node (ref "PS1") (pin "7") (pinfunction "GNDISO_2_7") (pintype "bidirectional"))
    )
    (net (code "14") (name "GND_ISO_TRIG") (class "Default")
      (node (ref "C16") (pin "2") (pinfunction "2_2") (pintype "passive"))
      (node (ref "C17") (pin "2") (pinfunction "2_2") (pintype "passive"))
      (node (ref "C24") (pin "2") (pinfunction "2_2") (pintype "passive"))
      (node (ref "C29") (pin "2") (pinfunction "2_2") (pintype "passive"))
      (node (ref "C30") (pin "2") (pinfunction "2_2") (pintype "passive"))
      (node (ref "DSUB3") (pin "9") (pinfunction "9_9") (pintype "passive"))
      (node (ref "JP5") (pin "10") (pinfunction "10_10") (pintype "passive"))
      (node (ref "JP5") (pin "9") (pinfunction "9_9") (pintype "passive"))
      (node (ref "L2") (pin "2") (pinfunction "2_2") (pintype "passive"))
      (node (ref "U7") (pin "10") (pinfunction "NIC_10") (pintype "bidirectional"))
      (node (ref "U7") (pin "15") (pinfunction "GND2_1_15") (pintype "power_in"))
      (node (ref "U7") (pin "9") (pinfunction "GND2_2_9") (pintype "power_in"))
      (node (ref "U8") (pin "10") (pinfunction "NIC_10") (pintype "bidirectional"))
      (node (ref "U8") (pin "15") (pinfunction "GND2_1_15") (pintype "power_in"))
      (node (ref "U8") (pin "9") (pinfunction "GND2_2_9") (pintype "power_in"))
    )
    (net (code "15") (name "IND_EX_1") (class "Default")
      (node (ref "U$2") (pin "15") (pinfunction "RX3_15_15") (pintype "bidirectional"))
      (node (ref "U8") (pin "4") (pinfunction "V1B_4") (pintype "input"))
    )
    (net (code "16") (name "IND_EX_1_ISO") (class "Default")
      (node (ref "DSUB3") (pin "6") (pinfunction "6_6") (pintype "passive"))
      (node (ref "JP5") (pin "3") (pinfunction "3_3") (pintype "passive"))
      (node (ref "U8") (pin "13") (pinfunction "VOB_13") (pintype "output"))
    )
    (net (code "17") (name "IND_EX_2") (class "Default")
      (node (ref "U$2") (pin "14") (pinfunction "TX3_14_14") (pintype "bidirectional"))
      (node (ref "U8") (pin "5") (pinfunction "V1C_5") (pintype "input"))
    )
    (net (code "18") (name "IND_EX_2_ISO") (class "Default")
      (node (ref "DSUB3") (pin "7") (pinfunction "7_7") (pintype "passive"))
      (node (ref "JP5") (pin "2") (pinfunction "2_2") (pintype "passive"))
      (node (ref "U8") (pin "12") (pinfunction "VOC_12") (pintype "output"))
    )
    (net (code "19") (name "IND_EX_3") (class "Default")
      (node (ref "U$2") (pin "2") (pinfunction "2_2") (pintype "bidirectional"))
      (node (ref "U8") (pin "6") (pinfunction "V1D_6") (pintype "input"))
    )
    (net (code "20") (name "IND_EX_3_ISO") (class "Default")
      (node (ref "DSUB3") (pin "8") (pinfunction "8_8") (pintype "passive"))
      (node (ref "JP5") (pin "1") (pinfunction "1_1") (pintype "passive"))
      (node (ref "U8") (pin "11") (pinfunction "VOD_11") (pintype "output"))
    )
    (net (code "21") (name "IND_FREQ") (class "Default")
      (node (ref "U$2") (pin "16") (pinfunction "TX2_16_16") (pintype "bidirectional"))
      (node (ref "U8") (pin "3") (pinfunction "V1A_3") (pintype "input"))
    )
    (net (code "22") (name "IND_FREQ_ISO") (class "Default")
      (node (ref "DSUB3") (pin "5") (pinfunction "5_5") (pintype "passive"))
      (node (ref "JP5") (pin "4") (pinfunction "4_4") (pintype "passive"))
      (node (ref "U8") (pin "14") (pinfunction "VOA_14") (pintype "output"))
    )
    (net (code "23") (name "IND_START") (class "Default")
      (node (ref "U$2") (pin "5") (pinfunction "5_5") (pintype "bidirectional"))
      (node (ref "U7") (pin "5") (pinfunction "V1C_5") (pintype "input"))
    )
    (net (code "24") (name "IND_START_ISO") (class "Default")
      (node (ref "DSUB3") (pin "3") (pinfunction "3_3") (pintype "passive"))
      (node (ref "JP5") (pin "6") (pinfunction "6_6") (pintype "passive"))
      (node (ref "U7") (pin "12") (pinfunction "VOC_12") (pintype "output"))
    )
    (net (code "25") (name "IND_STIM") (class "Default")
      (node (ref "U$2") (pin "4") (pinfunction "4_4") (pintype "bidirectional"))
      (node (ref "U7") (pin "4") (pinfunction "V1B_4") (pintype "input"))
    )
    (net (code "26") (name "IND_STIM_ISO") (class "Default")
      (node (ref "DSUB3") (pin "2") (pinfunction "2_2") (pintype "passive"))
      (node (ref "JP5") (pin "7") (pinfunction "7_7") (pintype "passive"))
      (node (ref "U7") (pin "13") (pinfunction "VOB_13") (pintype "output"))
    )
    (net (code "27") (name "IND_STOP") (class "Default")
      (node (ref "U$2") (pin "6") (pinfunction "6_6") (pintype "bidirectional"))
      (node (ref "U7") (pin "6") (pinfunction "V1D_6") (pintype "input"))
    )
    (net (code "28") (name "IND_STOP_ISO") (class "Default")
      (node (ref "DSUB3") (pin "4") (pinfunction "4_4") (pintype "passive"))
      (node (ref "JP5") (pin "5") (pinfunction "5_5") (pintype "passive"))
      (node (ref "U7") (pin "11") (pinfunction "VOD_11") (pintype "output"))
    )
    (net (code "29") (name "IND_SWITCH") (class "Default")
      (node (ref "U$2") (pin "3") (pinfunction "3_3") (pintype "bidirectional"))
      (node (ref "U7") (pin "3") (pinfunction "V1A_3") (pintype "input"))
    )
    (net (code "30") (name "IND_SWITCH_ISO") (class "Default")
      (node (ref "DSUB3") (pin "1") (pinfunction "1_1") (pintype "passive"))
      (node (ref "JP5") (pin "8") (pinfunction "8_8") (pintype "passive"))
      (node (ref "U7") (pin "14") (pinfunction "VOA_14") (pintype "output"))
    )
    (net (code "31") (name "I{slash}O_UPDATE") (class "Default")
      (node (ref "U$2") (pin "18") (pinfunction "TX1_18_18") (pintype "bidirectional"))
      (node (ref "U1") (pin "1") (pinfunction "I/O_UPDATE_1") (pintype "bidirectional"))
    )
    (net (code "32") (name "Net-(IOUT+-PadTP)") (class "Default")
      (node (ref "IOUT+") (pin "TP") (pinfunction "TP_TP") (pintype "input"))
      (node (ref "JP1") (pin "2") (pinfunction "2_2") (pintype "passive"))
      (node (ref "JP1") (pin "4") (pinfunction "4_4") (pintype "passive"))
      (node (ref "JP1") (pin "6") (pinfunction "6_6") (pintype "passive"))
      (node (ref "R2_H") (pin "2") (pinfunction "2_2") (pintype "passive"))
    )
    (net (code "33") (name "Net-(JP1-Pad1)") (class "Default")
      (node (ref "JP1") (pin "1") (pinfunction "1_1") (pintype "passive"))
      (node (ref "R_HG1") (pin "2") (pinfunction "2_2") (pintype "passive"))
    )
    (net (code "34") (name "Net-(JP1-Pad3)") (class "Default")
      (node (ref "JP1") (pin "3") (pinfunction "3_3") (pintype "passive"))
      (node (ref "R_HG2") (pin "2") (pinfunction "2_2") (pintype "passive"))
    )
    (net (code "35") (name "Net-(JP1-Pad5)") (class "Default")
      (node (ref "JP1") (pin "5") (pinfunction "5_5") (pintype "passive"))
      (node (ref "R_HG3") (pin "2") (pinfunction "2_2") (pintype "passive"))
    )
    (net (code "36") (name "Net-(U1-DACBP)") (class "Default")
      (node (ref "C2") (pin "2") (pinfunction "2_2") (pintype "passive"))
      (node (ref "U1") (pin "23") (pinfunction "DACBP_23") (pintype "input"))
    )
    (net (code "37") (name "Net-(U1-DAC_RSET)") (class "Default")
      (node (ref "R_SET1") (pin "2") (pinfunction "2_2") (pintype "passive"))
      (node (ref "U1") (pin "24") (pinfunction "DAC_RSET_24") (pintype "input"))
    )
    (net (code "38") (name "Net-(U1-IOUT)") (class "Default")
      (node (ref "R4_DAC") (pin "2") (pinfunction "2_2") (pintype "passive"))
      (node (ref "RG_DAC") (pin "1") (pinfunction "1_1") (pintype "passive"))
      (node (ref "RY_DAC") (pin "1") (pinfunction "1_1") (pintype "passive"))
      (node (ref "U1") (pin "21") (pinfunction "IOUT_21") (pintype "output"))
    )
    (net (code "39") (name "Net-(U1-LOOP_FILTER)") (class "Default")
      (node (ref "C38") (pin "2") (pinfunction "2_2") (pintype "passive"))
      (node (ref "U1") (pin "12") (pinfunction "LOOP_FILTER_12") (pintype "input"))
    )
    (net (code "40") (name "Net-(U1-~{IOUT})") (class "Default")
      (node (ref "R1_DAC") (pin "2") (pinfunction "2_2") (pintype "passive"))
      (node (ref "R2_DAC") (pin "2") (pinfunction "2_2") (pintype "passive"))
      (node (ref "RX_DAC") (pin "1") (pinfunction "1_1") (pintype "passive"))
      (node (ref "U1") (pin "20") (pinfunction "~{IOUT}_20") (pintype "output"))
    )
    (net (code "41") (name "Net-(U1-~{OSC{slash}}REFCLK)") (class "Default")
      (node (ref "C1") (pin "2") (pinfunction "2_2") (pintype "passive"))
      (node (ref "U1") (pin "8") (pinfunction "~{OSC/}REFCLK_8") (pintype "input"))
    )
    (net (code "42") (name "Net-(U2-SET)") (class "Default")
      (node (ref "R3") (pin "2") (pinfunction "2_2") (pintype "passive"))
      (node (ref "U2") (pin "3") (pinfunction "SET_3") (pintype "input"))
    )
    (net (code "43") (name "Net-(U6-BOOST)") (class "Default")
      (node (ref "R1") (pin "1") (pinfunction "1_1") (pintype "passive"))
      (node (ref "U6") (pin "1") (pinfunction "BOOST_1") (pintype "input"))
    )
    (net (code "44") (name "Net-(U6-CAP+)") (class "Default")
      (node (ref "C50") (pin "1") (pinfunction "1_1") (pintype "passive"))
      (node (ref "U6") (pin "2") (pinfunction "CAP+_2") (pintype "passive"))
    )
    (net (code "45") (name "Net-(U6-CAP-)") (class "Default")
      (node (ref "C50") (pin "2") (pinfunction "2_2") (pintype "passive"))
      (node (ref "U6") (pin "4") (pinfunction "CAP-_4") (pintype "passive"))
    )
    (net (code "46") (name "PS0") (class "Default")
      (node (ref "U$2") (pin "20") (pinfunction "SDA_20_20") (pintype "bidirectional"))
      (node (ref "U1") (pin "47") (pinfunction "PS0_47") (pintype "input"))
    )
    (net (code "47") (name "PS1") (class "Default")
      (node (ref "U$2") (pin "19") (pinfunction "RX1_19_19") (pintype "bidirectional"))
      (node (ref "U1") (pin "48") (pinfunction "PS1_48") (pintype "input"))
    )
    (net (code "48") (name "REFCLK") (class "Default")
      (node (ref "CLK") (pin "TP") (pinfunction "TP_TP") (pintype "input"))
      (node (ref "U1") (pin "9") (pinfunction "OSC/REFCLK_9") (pintype "input"))
      (node (ref "U2") (pin "5") (pinfunction "OUT_5") (pintype "output"))
    )
    (net (code "49") (name "RESET") (class "Default")
      (node (ref "U$2") (pin "21") (pinfunction "SCL_21_21") (pintype "bidirectional"))
      (node (ref "U1") (pin "36") (pinfunction "RESET_36") (pintype "input"))
    )
    (net (code "50") (name "SCLK") (class "Default")
      (node (ref "SCLK") (pin "TP") (pinfunction "TP_TP") (pintype "input"))
      (node (ref "U$2") (pin "SPCK") (pinfunction "SPCK_SPCK") (pintype "bidirectional"))
      (node (ref "U1") (pin "40") (pinfunction "SCLK_40") (pintype "input"))
    )
    (net (code "51") (name "SDIO") (class "Default")
      (node (ref "SDIO") (pin "TP") (pinfunction "TP_TP") (pintype "input"))
      (node (ref "U$2") (pin "MOSI") (pinfunction "MOSI_MOSI") (pintype "bidirectional"))
      (node (ref "U1") (pin "41") (pinfunction "SDIO_41") (pintype "input"))
    )
    (net (code "52") (name "SDO") (class "Default")
      (node (ref "SDO") (pin "TP") (pinfunction "TP_TP") (pintype "input"))
      (node (ref "U$2") (pin "MISO") (pinfunction "MISO_MISO") (pintype "bidirectional"))
      (node (ref "U1") (pin "38") (pinfunction "SDO_38") (pintype "output"))
    )
    (net (code "53") (name "SW_DIN+") (class "Default")
      (node (ref "DSUB2") (pin "3") (pinfunction "3_3") (pintype "passive"))
      (node (ref "U$2") (pin "10") (pinfunction "10_10") (pintype "bidirectional"))
    )
    (net (code "54") (name "SW_DIN-") (class "Default")
      (node (ref "DSUB2") (pin "7") (pinfunction "7_7") (pintype "passive"))
      (node (ref "U$2") (pin "11") (pinfunction "11_11") (pintype "bidirectional"))
    )
    (net (code "55") (name "SW_RESET") (class "Default")
      (node (ref "DSUB2") (pin "8") (pinfunction "8_8") (pintype "passive"))
      (node (ref "U$2") (pin "9") (pinfunction "9_9") (pintype "bidirectional"))
    )
    (net (code "56") (name "SW_SCLK") (class "Default")
      (node (ref "DSUB2") (pin "2") (pinfunction "2_2") (pintype "passive"))
      (node (ref "U$2") (pin "12") (pinfunction "12_12") (pintype "bidirectional"))
    )
    (net (code "57") (name "SW_SYNC") (class "Default")
      (node (ref "DSUB2") (pin "4") (pinfunction "4_4") (pintype "passive"))
      (node (ref "U$2") (pin "8") (pinfunction "8_8") (pintype "bidirectional"))
    )
    (net (code "58") (name "SW_TEST_1") (class "Default")
      (node (ref "DSUB2") (pin "5") (pinfunction "5_5") (pintype "passive"))
      (node (ref "R10") (pin "2") (pinfunction "2_2") (pintype "passive"))
      (node (ref "U$2") (pin "7") (pinfunction "7_7") (pintype "bidirectional"))
    )
    (net (code "59") (name "SW_TEST_2") (class "Default")
      (node (ref "DSUB2") (pin "1") (pinfunction "1_1") (pintype "passive"))
      (node (ref "R11") (pin "2") (pinfunction "2_2") (pintype "passive"))
      (node (ref "U$2") (pin "13") (pinfunction "13_13") (pintype "bidirectional"))
    )
    (net (code "60") (name "VBAT+") (class "Default")
      (node (ref "JP2") (pin "1") (pinfunction "1_1") (pintype "passive"))
      (node (ref "JP3") (pin "1") (pinfunction "1_1") (pintype "passive"))
      (node (ref "S3") (pin "6") (pinfunction "S1_6") (pintype "passive"))
    )
    (net (code "61") (name "VBAT-") (class "Default")
      (node (ref "JP4") (pin "2") (pinfunction "2_2") (pintype "passive"))
      (node (ref "JP6") (pin "2") (pinfunction "2_2") (pintype "passive"))
      (node (ref "S3") (pin "3") (pinfunction "S_3") (pintype "passive"))
    )
    (net (code "62") (name "VIN_NEG") (class "Default")
      (node (ref "C41") (pin "2") (pinfunction "2_2") (pintype "passive"))
      (node (ref "C42") (pin "2") (pinfunction "2_2") (pintype "passive"))
      (node (ref "IC3") (pin "4") (pinfunction "V-_4") (pintype "power_in"))
      (node (ref "S3") (pin "2") (pinfunction "P_2") (pintype "passive"))
      (node (ref "VIN_NEG") (pin "TP") (pinfunction "TP_TP") (pintype "input"))
    )
    (net (code "63") (name "VIN_POS") (class "Default")
      (node (ref "C39") (pin "2") (pinfunction "2_2") (pintype "passive"))
      (node (ref "C40") (pin "2") (pinfunction "2_2") (pintype "passive"))
      (node (ref "C46") (pin "1") (pinfunction "1_1") (pintype "passive"))
      (node (ref "C48") (pin "1") (pinfunction "1_1") (pintype "passive"))
      (node (ref "IC1") (pin "3") (pinfunction "VIN_3") (pintype "input"))
      (node (ref "IC2") (pin "3") (pinfunction "VIN_3") (pintype "input"))
      (node (ref "IC3") (pin "8") (pinfunction "V+_8") (pintype "power_in"))
      (node (ref "R1") (pin "2") (pinfunction "2_2") (pintype "passive"))
      (node (ref "S3") (pin "5") (pinfunction "P1_5") (pintype "passive"))
      (node (ref "U6") (pin "8") (pinfunction "V+_8") (pintype "power_in"))
      (node (ref "VIN_POS") (pin "TP") (pinfunction "TP_TP") (pintype "input"))
    )
    (net (code "64") (name "V_ISO_INIT") (class "Default")
      (node (ref "C25") (pin "1") (pinfunction "1_1") (pintype "passive"))
      (node (ref "L1") (pin "1") (pinfunction "1_1") (pintype "passive"))
      (node (ref "PS1") (pin "6") (pinfunction "VISO_6") (pintype "bidirectional"))
      (node (ref "PS1") (pin "8") (pinfunction "VSEL_8") (pintype "bidirectional"))
    )
    (net (code "65") (name "V_ISO_TRIG") (class "Default")
      (node (ref "C16") (pin "1") (pinfunction "1_1") (pintype "passive"))
      (node (ref "C17") (pin "1") (pinfunction "1_1") (pintype "passive"))
      (node (ref "C24") (pin "1") (pinfunction "1_1") (pintype "passive"))
      (node (ref "C29") (pin "1") (pinfunction "1_1") (pintype "passive"))
      (node (ref "C30") (pin "1") (pinfunction "1_1") (pintype "passive"))
      (node (ref "L1") (pin "2") (pinfunction "2_2") (pintype "passive"))
      (node (ref "U7") (pin "16") (pinfunction "VDD_16") (pintype "power_in"))
      (node (ref "U8") (pin "16") (pinfunction "VDD_16") (pintype "power_in"))
    )
    (net (code "66") (name "unconnected-(U$2-5V_SPI-Pad5V_2)") (class "Default")
      (node (ref "U$2") (pin "5V_2") (pinfunction "5V_SPI_5V_2") (pintype "bidirectional"))
    )
    (net (code "67") (name "unconnected-(U$2-GND-PadGND_1)") (class "Default")
      (node (ref "U$2") (pin "GND_1") (pinfunction "GND_GND_1") (pintype "bidirectional"))
    )
    (net (code "68") (name "unconnected-(U$2-MASTER_R_SPI-PadMASTER_RESET_SPI)") (class "Default")
      (node (ref "U$2") (pin "MASTER_RESET_SPI") (pinfunction "MASTER_R_SPI_MASTER_RESET_SPI") (pintype "bidirectional"))
    )
    (net (code "69") (name "unconnected-(U$2-NC-PadNC_2)") (class "Default")
      (node (ref "U$2") (pin "NC_2") (pinfunction "NC_NC_2") (pintype "no_connect"))
    )
    (net (code "70") (name "unconnected-(U$2-PadAREF)") (class "Default")
      (node (ref "U$2") (pin "AREF") (pinfunction "AREF_AREF") (pintype "bidirectional"))
    )
    (net (code "71") (name "unconnected-(U$2-PadIOREF)") (class "Default")
      (node (ref "U$2") (pin "IOREF") (pinfunction "IOREF_IOREF") (pintype "bidirectional"))
    )
    (net (code "72") (name "unconnected-(U$2-PadRESET)") (class "Default")
      (node (ref "U$2") (pin "RESET") (pinfunction "RESET_RESET") (pintype "bidirectional"))
    )
    (net (code "73") (name "unconnected-(U$2-PadSCL1)") (class "Default")
      (node (ref "U$2") (pin "SCL1") (pinfunction "SCL1_SCL1") (pintype "bidirectional"))
    )
    (net (code "74") (name "unconnected-(U$2-PadSDA1)") (class "Default")
      (node (ref "U$2") (pin "SDA1") (pinfunction "SDA1_SDA1") (pintype "bidirectional"))
    )
    (net (code "75") (name "unconnected-(U$2-PadVIN)") (class "Default")
      (node (ref "U$2") (pin "VIN") (pinfunction "VIN_VIN") (pintype "bidirectional"))
    )
    (net (code "76") (name "unconnected-(U$2-RX0<0-Pad0)") (class "Default")
      (node (ref "U$2") (pin "0") (pinfunction "RX0<0_0") (pintype "bidirectional"))
    )
    (net (code "77") (name "unconnected-(U$2-TX0>1-Pad1)") (class "Default")
      (node (ref "U$2") (pin "1") (pinfunction "TX0>1_1") (pintype "bidirectional"))
    )
    (net (code "78") (name "unconnected-(U1-COMP_IN-Pad30)") (class "Default")
      (node (ref "U1") (pin "30") (pinfunction "COMP_IN_30") (pintype "input"))
    )
    (net (code "79") (name "unconnected-(U1-COMP_OUT-Pad28)") (class "Default")
      (node (ref "U1") (pin "28") (pinfunction "COMP_OUT_28") (pintype "passive"))
    )
    (net (code "80") (name "unconnected-(U1-CRYSTAL_OUT-Pad10)") (class "Default")
      (node (ref "U1") (pin "10") (pinfunction "CRYSTAL_OUT_10") (pintype "output"))
    )
    (net (code "81") (name "unconnected-(U1-SYNC_CLK-Pad45)") (class "Default")
      (node (ref "U1") (pin "45") (pinfunction "SYNC_CLK_45") (pintype "input"))
    )
    (net (code "82") (name "unconnected-(U1-SYNC_IN-Pad44)") (class "Default")
      (node (ref "U1") (pin "44") (pinfunction "SYNC_IN_44") (pintype "input"))
    )
    (net (code "83") (name "unconnected-(U1-~{COMP_IN}-Pad31)") (class "Default")
      (node (ref "U1") (pin "31") (pinfunction "~{COMP_IN}_31") (pintype "input"))
    )
    (net (code "84") (name "unconnected-(U6-LV-Pad6)") (class "Default")
      (node (ref "U6") (pin "6") (pinfunction "LV_6") (pintype "input"))
    )
    (net (code "85") (name "unconnected-(U6-OSC-Pad7)") (class "Default")
      (node (ref "U6") (pin "7") (pinfunction "OSC_7") (pintype "input"))
    )
    (net (code "86") (name "~{CS}") (class "Default")
      (node (ref "U$2") (pin "17") (pinfunction "RX2_17_17") (pintype "bidirectional"))
      (node (ref "U1") (pin "39") (pinfunction "~{CS}_39") (pintype "input"))
    )
  )
)
